# BluetoothModule.net
KiCad netlist of a schematic drawn in EAGLE
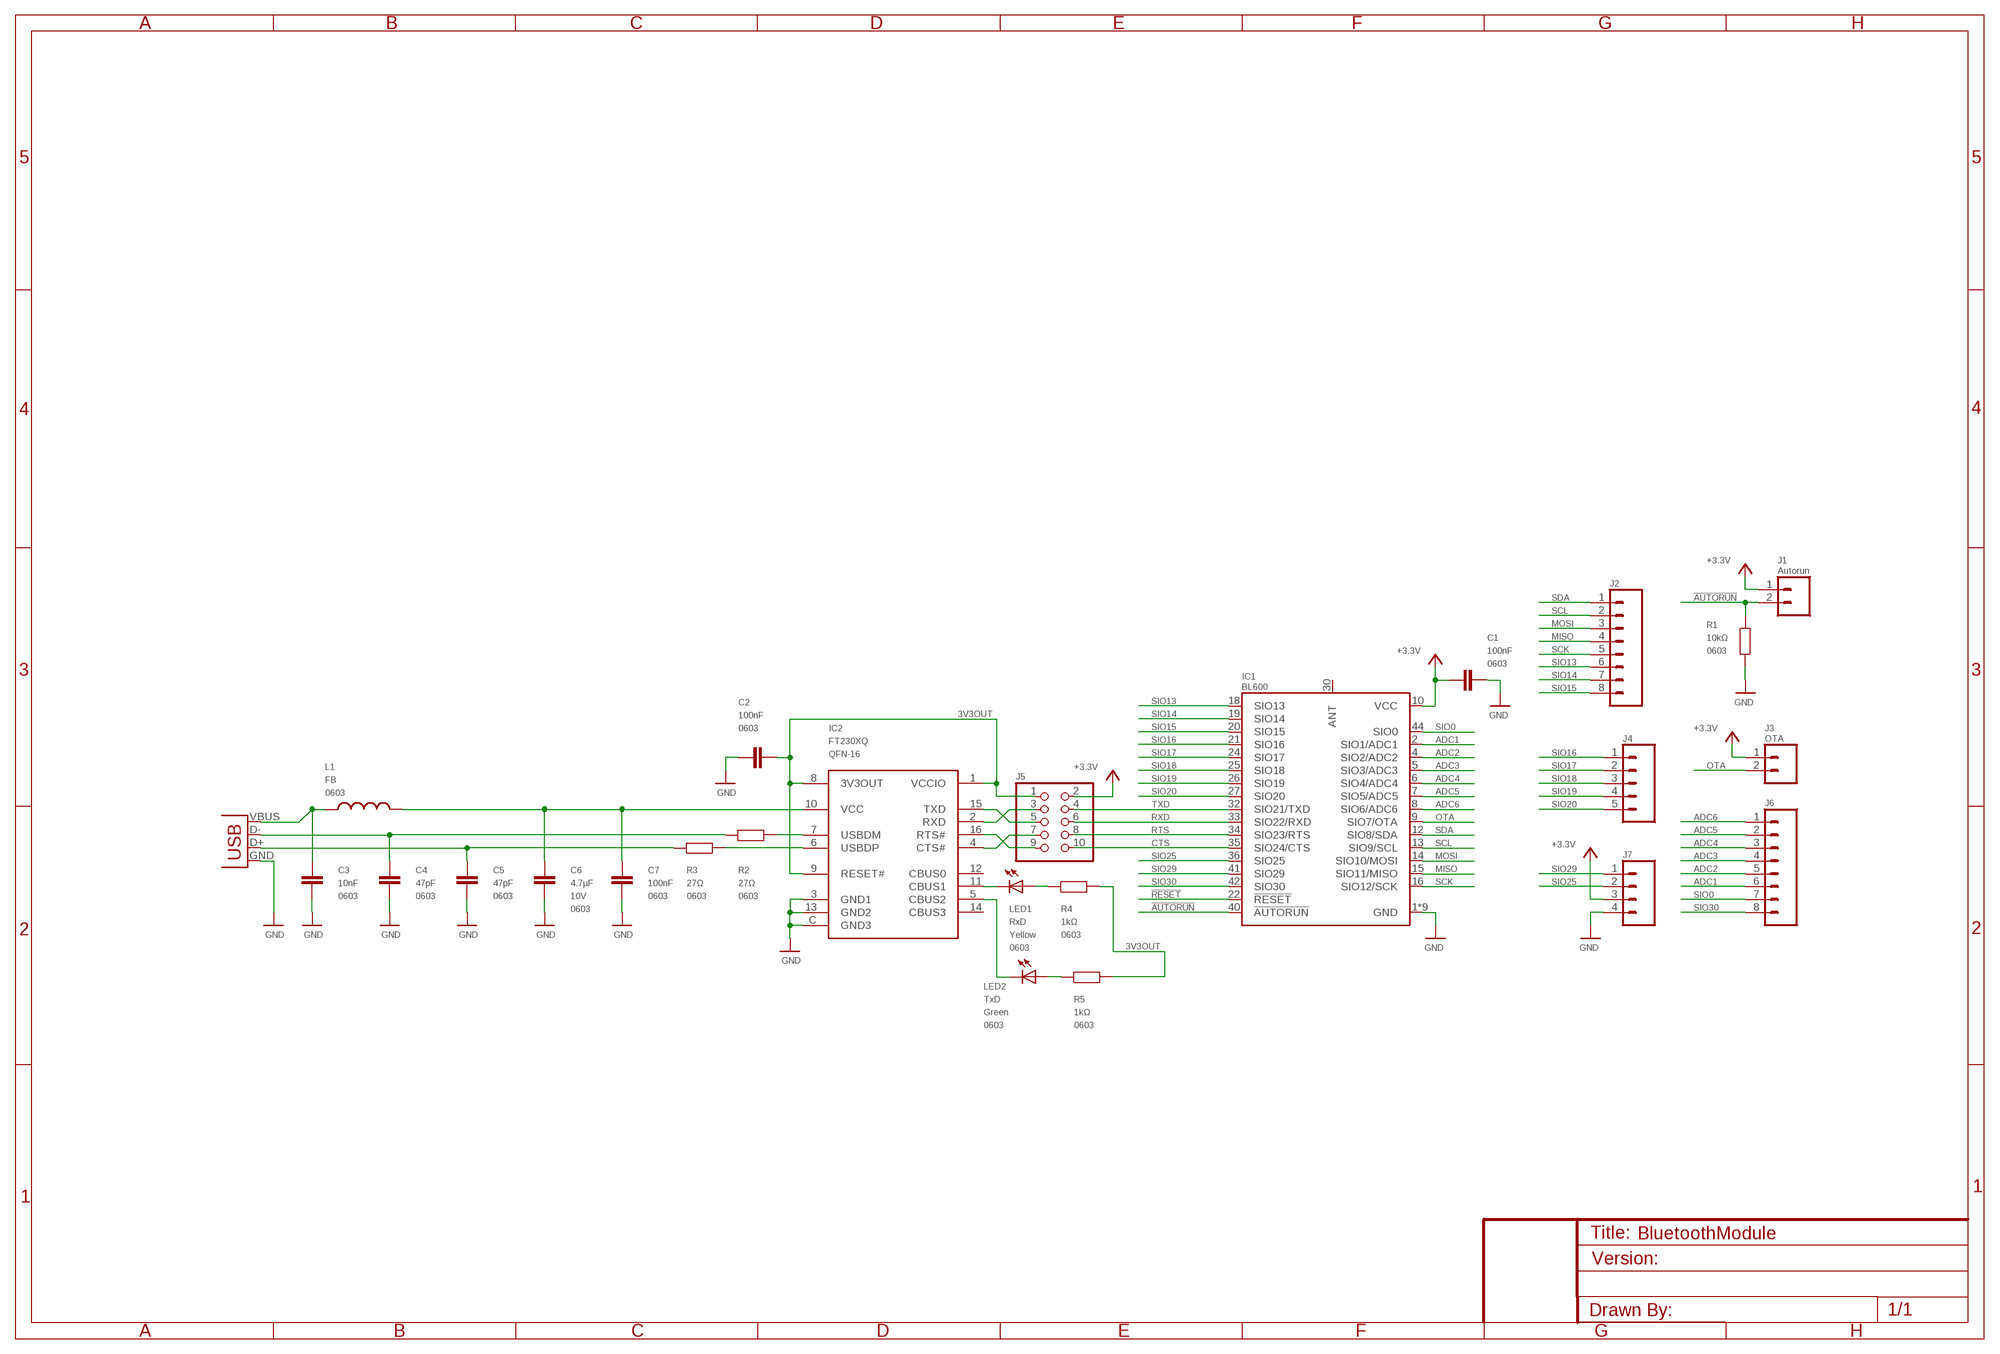
[diagram p0: schematic, sheet 1]

(export (version "E")
  (design (tool "Eeschema 10.0.6"))
  (components
    (comp (ref "C1")
      (value "100nF")
      (footprint "eagle-import:0603")
      (fields (field (name "PACKAGE") "0603"))
      (libsource (lib "eagle-import") (part "CAP0603"))
    )
    (comp (ref "C2")
      (value "100nF")
      (footprint "eagle-import:0603")
      (fields (field (name "PACKAGE") "0603"))
      (libsource (lib "eagle-import") (part "CAP0603"))
    )
    (comp (ref "C3")
      (value "10nF")
      (footprint "eagle-import:0603")
      (fields (field (name "PACKAGE") "0603"))
      (libsource (lib "eagle-import") (part "CAP0603"))
    )
    (comp (ref "C4")
      (value "47pF")
      (footprint "eagle-import:0603")
      (fields (field (name "PACKAGE") "0603"))
      (libsource (lib "eagle-import") (part "CAP0603"))
    )
    (comp (ref "C5")
      (value "47pF")
      (footprint "eagle-import:0603")
      (fields (field (name "PACKAGE") "0603"))
      (libsource (lib "eagle-import") (part "CAP0603"))
    )
    (comp (ref "C6")
      (value "4.7µF")
      (footprint "eagle-import:0603")
      (fields (field (name "PACKAGE") "0603") (field (name "VOLTAGE") "10V"))
      (libsource (lib "eagle-import") (part "CAP0603"))
    )
    (comp (ref "C7")
      (value "100nF")
      (footprint "eagle-import:0603")
      (fields (field (name "PACKAGE") "0603"))
      (libsource (lib "eagle-import") (part "CAP0603"))
    )
    (comp (ref "IC1")
      (value "BL600")
      (footprint "eagle-import:BL600-SA")
      (libsource (lib "eagle-import") (part "BL600"))
    )
    (comp (ref "IC2")
      (value "FT230XQ")
      (footprint "eagle-import:QFN4X4-16")
      (fields (field (name "PACKAGE") "QFN-16") (field (name "VALUE2") "FT230XQ"))
      (libsource (lib "eagle-import") (part "FT230XQ"))
    )
    (comp (ref "J1")
      (value "Autorun")
      (footprint "eagle-import:1X02")
      (libsource (lib "eagle-import") (part "M02PTH"))
    )
    (comp (ref "J2")
      (value "M08STD")
      (footprint "eagle-import:1X08")
      (libsource (lib "eagle-import") (part "M08STD"))
    )
    (comp (ref "J3")
      (value "OTA")
      (footprint "eagle-import:1X02")
      (libsource (lib "eagle-import") (part "M02PTH"))
    )
    (comp (ref "J4")
      (value "M05PTH")
      (footprint "eagle-import:1X05")
      (libsource (lib "eagle-import") (part "M05PTH"))
    )
    (comp (ref "J5")
      (value "PINHD-2X5")
      (footprint "eagle-import:2X05")
      (libsource (lib "eagle-import") (part "PINHD-2X5"))
    )
    (comp (ref "J6")
      (value "M08STD")
      (footprint "eagle-import:1X08")
      (libsource (lib "eagle-import") (part "M08STD"))
    )
    (comp (ref "J7")
      (value "M04PTH")
      (footprint "eagle-import:1X04")
      (libsource (lib "eagle-import") (part "M04PTH"))
    )
    (comp (ref "J8")
      (value "USB")
      (footprint "eagle-import:USB-MICROB")
      (libsource (lib "eagle-import") (part "USB-MICROB"))
    )
    (comp (ref "L1")
      (value "FB")
      (footprint "eagle-import:0603")
      (fields (field (name "PACKAGE") "0603"))
      (libsource (lib "eagle-import") (part "INDUCTOR0603"))
    )
    (comp (ref "LED1")
      (value "RxD")
      (footprint "eagle-import:LED-0603")
      (fields (field (name "COLOR") "Yellow") (field (name "PACKAGE") "0603"))
      (libsource (lib "eagle-import") (part "LED0603"))
    )
    (comp (ref "LED2")
      (value "TxD")
      (footprint "eagle-import:LED-0603")
      (fields (field (name "COLOR") "Green") (field (name "PACKAGE") "0603"))
      (libsource (lib "eagle-import") (part "LED0603"))
    )
    (comp (ref "R1")
      (value "10kΩ")
      (footprint "eagle-import:0603")
      (fields (field (name "PACKAGE") "0603"))
      (libsource (lib "eagle-import") (part "RESISTOR0603"))
    )
    (comp (ref "R2")
      (value "27Ω")
      (footprint "eagle-import:0603")
      (fields (field (name "PACKAGE") "0603"))
      (libsource (lib "eagle-import") (part "RESISTOR0603"))
    )
    (comp (ref "R3")
      (value "27Ω")
      (footprint "eagle-import:0603")
      (fields (field (name "PACKAGE") "0603"))
      (libsource (lib "eagle-import") (part "RESISTOR0603"))
    )
    (comp (ref "R4")
      (value "1kΩ")
      (footprint "eagle-import:0603")
      (fields (field (name "PACKAGE") "0603"))
      (libsource (lib "eagle-import") (part "RESISTOR0603"))
    )
    (comp (ref "R5")
      (value "1kΩ")
      (footprint "eagle-import:0603")
      (fields (field (name "PACKAGE") "0603"))
      (libsource (lib "eagle-import") (part "RESISTOR0603"))
    )
  )
  (nets
    (net (code "1") (name "+3.3V") (class "Default")
      (node (ref "C1") (pin "2") (pinfunction "2_2") (pintype "passive"))
      (node (ref "IC1") (pin "10") (pinfunction "VCC_10") (pintype "bidirectional"))
      (node (ref "J1") (pin "1") (pinfunction "1_1") (pintype "passive"))
      (node (ref "J3") (pin "1") (pinfunction "1_1") (pintype "passive"))
      (node (ref "J5") (pin "2") (pinfunction "2_2") (pintype "passive"))
      (node (ref "J7") (pin "3") (pinfunction "3_3") (pintype "passive"))
    )
    (net (code "2") (name "/3V3OUT") (class "Default")
      (node (ref "C2") (pin "2") (pinfunction "2_2") (pintype "passive"))
      (node (ref "IC2") (pin "1") (pinfunction "VCCIO_1") (pintype "input"))
      (node (ref "IC2") (pin "8") (pinfunction "3V3OUT_8") (pintype "output"))
      (node (ref "IC2") (pin "9") (pinfunction "RESET#_9") (pintype "input"))
      (node (ref "J5") (pin "1") (pinfunction "1_1") (pintype "passive"))
      (node (ref "R4") (pin "2") (pinfunction "2_2") (pintype "passive"))
      (node (ref "R5") (pin "2") (pinfunction "2_2") (pintype "passive"))
    )
    (net (code "3") (name "/ADC1") (class "Default")
      (node (ref "IC1") (pin "2") (pinfunction "SIO1/ADC1_2") (pintype "bidirectional"))
      (node (ref "J6") (pin "6") (pinfunction "6_6") (pintype "passive"))
    )
    (net (code "4") (name "/ADC2") (class "Default")
      (node (ref "IC1") (pin "4") (pinfunction "SIO2/ADC2_4") (pintype "bidirectional"))
      (node (ref "J6") (pin "5") (pinfunction "5_5") (pintype "passive"))
    )
    (net (code "5") (name "/ADC3") (class "Default")
      (node (ref "IC1") (pin "5") (pinfunction "SIO3/ADC3_5") (pintype "bidirectional"))
      (node (ref "J6") (pin "4") (pinfunction "4_4") (pintype "passive"))
    )
    (net (code "6") (name "/ADC4") (class "Default")
      (node (ref "IC1") (pin "6") (pinfunction "SIO4/ADC4_6") (pintype "bidirectional"))
      (node (ref "J6") (pin "3") (pinfunction "3_3") (pintype "passive"))
    )
    (net (code "7") (name "/ADC5") (class "Default")
      (node (ref "IC1") (pin "7") (pinfunction "SIO5/ADC5_7") (pintype "bidirectional"))
      (node (ref "J6") (pin "2") (pinfunction "2_2") (pintype "passive"))
    )
    (net (code "8") (name "/ADC6") (class "Default")
      (node (ref "IC1") (pin "8") (pinfunction "SIO6/ADC6_8") (pintype "bidirectional"))
      (node (ref "J6") (pin "1") (pinfunction "1_1") (pintype "passive"))
    )
    (net (code "9") (name "/CTS") (class "Default")
      (node (ref "IC1") (pin "35") (pinfunction "SIO24/CTS_35") (pintype "bidirectional"))
      (node (ref "J5") (pin "10") (pinfunction "10_10") (pintype "passive"))
    )
    (net (code "10") (name "/MISO") (class "Default")
      (node (ref "IC1") (pin "15") (pinfunction "SIO11/MISO_15") (pintype "bidirectional"))
      (node (ref "J2") (pin "4") (pinfunction "4_4") (pintype "passive"))
    )
    (net (code "11") (name "/MOSI") (class "Default")
      (node (ref "IC1") (pin "14") (pinfunction "SIO10/MOSI_14") (pintype "bidirectional"))
      (node (ref "J2") (pin "3") (pinfunction "3_3") (pintype "passive"))
    )
    (net (code "12") (name "/OTA") (class "Default")
      (node (ref "IC1") (pin "9") (pinfunction "SIO7/OTA_9") (pintype "bidirectional"))
      (node (ref "J3") (pin "2") (pinfunction "2_2") (pintype "passive"))
    )
    (net (code "13") (name "/RTS") (class "Default")
      (node (ref "IC1") (pin "34") (pinfunction "SIO23/RTS_34") (pintype "bidirectional"))
      (node (ref "J5") (pin "8") (pinfunction "8_8") (pintype "passive"))
    )
    (net (code "14") (name "/RXD") (class "Default")
      (node (ref "IC1") (pin "33") (pinfunction "SIO22/RXD_33") (pintype "bidirectional"))
      (node (ref "J5") (pin "6") (pinfunction "6_6") (pintype "passive"))
    )
    (net (code "15") (name "/SCK") (class "Default")
      (node (ref "IC1") (pin "16") (pinfunction "SIO12/SCK_16") (pintype "bidirectional"))
      (node (ref "J2") (pin "5") (pinfunction "5_5") (pintype "passive"))
    )
    (net (code "16") (name "/SCL") (class "Default")
      (node (ref "IC1") (pin "13") (pinfunction "SIO9/SCL_13") (pintype "bidirectional"))
      (node (ref "J2") (pin "2") (pinfunction "2_2") (pintype "passive"))
    )
    (net (code "17") (name "/SDA") (class "Default")
      (node (ref "IC1") (pin "12") (pinfunction "SIO8/SDA_12") (pintype "bidirectional"))
      (node (ref "J2") (pin "1") (pinfunction "1_1") (pintype "passive"))
    )
    (net (code "18") (name "/SIO0") (class "Default")
      (node (ref "IC1") (pin "44") (pinfunction "SIO0_44") (pintype "bidirectional"))
      (node (ref "J6") (pin "7") (pinfunction "7_7") (pintype "passive"))
    )
    (net (code "19") (name "/SIO13") (class "Default")
      (node (ref "IC1") (pin "18") (pinfunction "SIO13_18") (pintype "bidirectional"))
      (node (ref "J2") (pin "6") (pinfunction "6_6") (pintype "passive"))
    )
    (net (code "20") (name "/SIO14") (class "Default")
      (node (ref "IC1") (pin "19") (pinfunction "SIO14_19") (pintype "bidirectional"))
      (node (ref "J2") (pin "7") (pinfunction "7_7") (pintype "passive"))
    )
    (net (code "21") (name "/SIO15") (class "Default")
      (node (ref "IC1") (pin "20") (pinfunction "SIO15_20") (pintype "bidirectional"))
      (node (ref "J2") (pin "8") (pinfunction "8_8") (pintype "passive"))
    )
    (net (code "22") (name "/SIO16") (class "Default")
      (node (ref "IC1") (pin "21") (pinfunction "SIO16_21") (pintype "bidirectional"))
      (node (ref "J4") (pin "1") (pinfunction "1_1") (pintype "passive"))
    )
    (net (code "23") (name "/SIO17") (class "Default")
      (node (ref "IC1") (pin "24") (pinfunction "SIO17_24") (pintype "bidirectional"))
      (node (ref "J4") (pin "2") (pinfunction "2_2") (pintype "passive"))
    )
    (net (code "24") (name "/SIO18") (class "Default")
      (node (ref "IC1") (pin "25") (pinfunction "SIO18_25") (pintype "bidirectional"))
      (node (ref "J4") (pin "3") (pinfunction "3_3") (pintype "passive"))
    )
    (net (code "25") (name "/SIO19") (class "Default")
      (node (ref "IC1") (pin "26") (pinfunction "SIO19_26") (pintype "bidirectional"))
      (node (ref "J4") (pin "4") (pinfunction "4_4") (pintype "passive"))
    )
    (net (code "26") (name "/SIO20") (class "Default")
      (node (ref "IC1") (pin "27") (pinfunction "SIO20_27") (pintype "bidirectional"))
      (node (ref "J4") (pin "5") (pinfunction "5_5") (pintype "passive"))
    )
    (net (code "27") (name "/SIO25") (class "Default")
      (node (ref "IC1") (pin "36") (pinfunction "SIO25_36") (pintype "bidirectional"))
      (node (ref "J7") (pin "2") (pinfunction "2_2") (pintype "passive"))
    )
    (net (code "28") (name "/SIO29") (class "Default")
      (node (ref "IC1") (pin "41") (pinfunction "SIO29_41") (pintype "bidirectional"))
      (node (ref "J7") (pin "1") (pinfunction "1_1") (pintype "passive"))
    )
    (net (code "29") (name "/SIO30") (class "Default")
      (node (ref "IC1") (pin "42") (pinfunction "SIO30_42") (pintype "bidirectional"))
      (node (ref "J6") (pin "8") (pinfunction "8_8") (pintype "passive"))
    )
    (net (code "30") (name "/TXD") (class "Default")
      (node (ref "IC1") (pin "32") (pinfunction "SIO21/TXD_32") (pintype "bidirectional"))
      (node (ref "J5") (pin "4") (pinfunction "4_4") (pintype "passive"))
    )
    (net (code "31") (name "/~{AUTORUN}") (class "Default")
      (node (ref "IC1") (pin "40") (pinfunction "~{AUTORUN}_40") (pintype "bidirectional"))
      (node (ref "J1") (pin "2") (pinfunction "2_2") (pintype "passive"))
      (node (ref "R1") (pin "2") (pinfunction "2_2") (pintype "passive"))
    )
    (net (code "32") (name "/~{RESET}") (class "Default")
      (node (ref "IC1") (pin "22") (pinfunction "~{RESET}_22") (pintype "bidirectional"))
    )
    (net (code "33") (name "GND") (class "Default")
      (node (ref "C1") (pin "1") (pinfunction "1_1") (pintype "passive"))
      (node (ref "C2") (pin "1") (pinfunction "1_1") (pintype "passive"))
      (node (ref "C3") (pin "1") (pinfunction "1_1") (pintype "passive"))
      (node (ref "C4") (pin "1") (pinfunction "1_1") (pintype "passive"))
      (node (ref "C5") (pin "1") (pinfunction "1_1") (pintype "passive"))
      (node (ref "C6") (pin "1") (pinfunction "1_1") (pintype "passive"))
      (node (ref "C7") (pin "1") (pinfunction "1_1") (pintype "passive"))
      (node (ref "IC1") (pin "1") (pinfunction "GND_1") (pintype "bidirectional"))
      (node (ref "IC1") (pin "11") (pinfunction "GND_11") (pintype "bidirectional"))
      (node (ref "IC1") (pin "17") (pinfunction "GND_17") (pintype "bidirectional"))
      (node (ref "IC1") (pin "28") (pinfunction "GND_28") (pintype "bidirectional"))
      (node (ref "IC1") (pin "29") (pinfunction "GND_29") (pintype "bidirectional"))
      (node (ref "IC1") (pin "3") (pinfunction "GND_3") (pintype "bidirectional"))
      (node (ref "IC1") (pin "31") (pinfunction "GND_31") (pintype "bidirectional"))
      (node (ref "IC1") (pin "37") (pinfunction "GND_37") (pintype "bidirectional"))
      (node (ref "IC1") (pin "43") (pinfunction "GND_43") (pintype "bidirectional"))
      (node (ref "IC2") (pin "13") (pinfunction "GND2_13") (pintype "power_in"))
      (node (ref "IC2") (pin "3") (pinfunction "GND1_3") (pintype "power_in"))
      (node (ref "IC2") (pin "C") (pinfunction "GND3_C") (pintype "power_in"))
      (node (ref "J7") (pin "4") (pinfunction "4_4") (pintype "passive"))
      (node (ref "J8") (pin "GND") (pinfunction "GND_GND") (pintype "bidirectional"))
      (node (ref "R1") (pin "1") (pinfunction "1_1") (pintype "passive"))
    )
    (net (code "34") (name "Net-(C3-Pad2)") (class "Default")
      (node (ref "C3") (pin "2") (pinfunction "2_2") (pintype "passive"))
      (node (ref "J8") (pin "VBUS") (pinfunction "VBUS_VBUS") (pintype "bidirectional"))
      (node (ref "L1") (pin "1") (pinfunction "1_1") (pintype "passive"))
    )
    (net (code "35") (name "Net-(C4-Pad2)") (class "Default")
      (node (ref "C4") (pin "2") (pinfunction "2_2") (pintype "passive"))
      (node (ref "J8") (pin "D-") (pinfunction "D-_D-") (pintype "bidirectional"))
      (node (ref "R2") (pin "1") (pinfunction "1_1") (pintype "passive"))
    )
    (net (code "36") (name "Net-(C5-Pad2)") (class "Default")
      (node (ref "C5") (pin "2") (pinfunction "2_2") (pintype "passive"))
      (node (ref "J8") (pin "D+") (pinfunction "D+_D+") (pintype "bidirectional"))
      (node (ref "R3") (pin "1") (pinfunction "1_1") (pintype "passive"))
    )
    (net (code "37") (name "Net-(IC2-CBUS1)") (class "Default")
      (node (ref "IC2") (pin "11") (pinfunction "CBUS1_11") (pintype "bidirectional"))
      (node (ref "LED1") (pin "C") (pinfunction "C_C") (pintype "passive"))
    )
    (net (code "38") (name "Net-(IC2-CBUS2)") (class "Default")
      (node (ref "IC2") (pin "5") (pinfunction "CBUS2_5") (pintype "bidirectional"))
      (node (ref "LED2") (pin "C") (pinfunction "C_C") (pintype "passive"))
    )
    (net (code "39") (name "Net-(IC2-CTS#)") (class "Default")
      (node (ref "IC2") (pin "4") (pinfunction "CTS#_4") (pintype "bidirectional"))
      (node (ref "J5") (pin "7") (pinfunction "7_7") (pintype "passive"))
    )
    (net (code "40") (name "Net-(IC2-RTS#)") (class "Default")
      (node (ref "IC2") (pin "16") (pinfunction "RTS#_16") (pintype "bidirectional"))
      (node (ref "J5") (pin "9") (pinfunction "9_9") (pintype "passive"))
    )
    (net (code "41") (name "Net-(IC2-RXD)") (class "Default")
      (node (ref "IC2") (pin "2") (pinfunction "RXD_2") (pintype "input"))
      (node (ref "J5") (pin "3") (pinfunction "3_3") (pintype "passive"))
    )
    (net (code "42") (name "Net-(IC2-TXD)") (class "Default")
      (node (ref "IC2") (pin "15") (pinfunction "TXD_15") (pintype "output"))
      (node (ref "J5") (pin "5") (pinfunction "5_5") (pintype "passive"))
    )
    (net (code "43") (name "Net-(IC2-USBDM)") (class "Default")
      (node (ref "IC2") (pin "7") (pinfunction "USBDM_7") (pintype "bidirectional"))
      (node (ref "R2") (pin "2") (pinfunction "2_2") (pintype "passive"))
    )
    (net (code "44") (name "Net-(IC2-USBDP)") (class "Default")
      (node (ref "IC2") (pin "6") (pinfunction "USBDP_6") (pintype "bidirectional"))
      (node (ref "R3") (pin "2") (pinfunction "2_2") (pintype "passive"))
    )
    (net (code "45") (name "Net-(IC2-VCC)") (class "Default")
      (node (ref "C6") (pin "2") (pinfunction "2_2") (pintype "passive"))
      (node (ref "C7") (pin "2") (pinfunction "2_2") (pintype "passive"))
      (node (ref "IC2") (pin "10") (pinfunction "VCC_10") (pintype "power_in"))
      (node (ref "L1") (pin "2") (pinfunction "2_2") (pintype "passive"))
    )
    (net (code "46") (name "Net-(LED1-PadA)") (class "Default")
      (node (ref "LED1") (pin "A") (pinfunction "A_A") (pintype "passive"))
      (node (ref "R4") (pin "1") (pinfunction "1_1") (pintype "passive"))
    )
    (net (code "47") (name "Net-(LED2-PadA)") (class "Default")
      (node (ref "LED2") (pin "A") (pinfunction "A_A") (pintype "passive"))
      (node (ref "R5") (pin "1") (pinfunction "1_1") (pintype "passive"))
    )
    (net (code "48") (name "unconnected-(IC1-ANT-Pad30)") (class "Default")
      (node (ref "IC1") (pin "30") (pinfunction "ANT_30") (pintype "bidirectional"))
    )
    (net (code "49") (name "unconnected-(IC2-CBUS0-Pad12)") (class "Default")
      (node (ref "IC2") (pin "12") (pinfunction "CBUS0_12") (pintype "bidirectional"))
    )
    (net (code "50") (name "unconnected-(IC2-CBUS3-Pad14)") (class "Default")
      (node (ref "IC2") (pin "14") (pinfunction "CBUS3_14") (pintype "bidirectional"))
    )
  )
)
